# Rainbow_F103C_Sch.net
KiCad netlist of a schematic drawn in Altium Designer
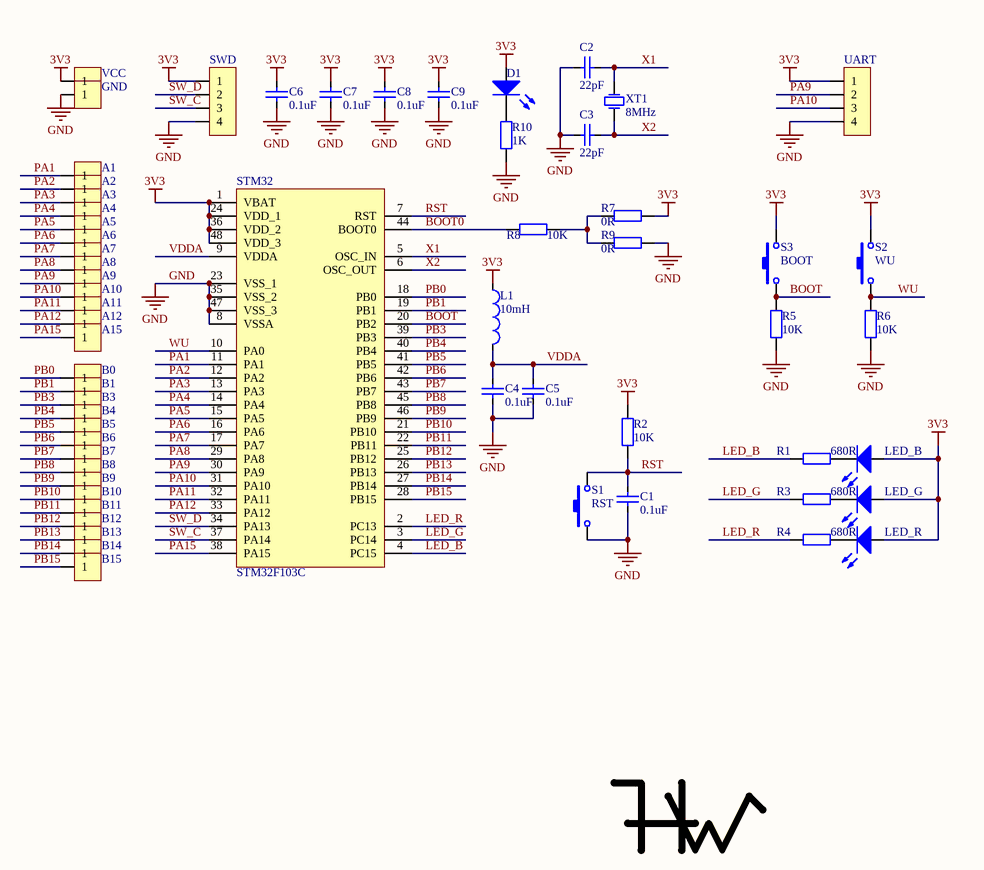
[diagram p0: Rainbow F103C_Sch.SchDoc]

(export (version "E")
  (design (tool "Eeschema 10.0.6"))
  (components
    (comp (ref "A1")
      (value "HDR1X1_180_2.54")
      (footprint "PCB_Connector:HDR1X1_180_2.54")
      (description "Header")
      (libsource (lib "SCH_Connector") (part "HDR1X1_180_2.54"))
    )
    (comp (ref "A2")
      (value "HDR1X1_180_2.54")
      (footprint "PCB_Connector:HDR1X1_180_2.54")
      (description "Header")
      (libsource (lib "SCH_Connector") (part "HDR1X1_180_2.54"))
    )
    (comp (ref "A3")
      (value "HDR1X1_180_2.54")
      (footprint "PCB_Connector:HDR1X1_180_2.54")
      (description "Header")
      (libsource (lib "SCH_Connector") (part "HDR1X1_180_2.54"))
    )
    (comp (ref "A4")
      (value "HDR1X1_180_2.54")
      (footprint "PCB_Connector:HDR1X1_180_2.54")
      (description "Header")
      (libsource (lib "SCH_Connector") (part "HDR1X1_180_2.54"))
    )
    (comp (ref "A5")
      (value "HDR1X1_180_2.54")
      (footprint "PCB_Connector:HDR1X1_180_2.54")
      (description "Header")
      (libsource (lib "SCH_Connector") (part "HDR1X1_180_2.54"))
    )
    (comp (ref "A6")
      (value "HDR1X1_180_2.54")
      (footprint "PCB_Connector:HDR1X1_180_2.54")
      (description "Header")
      (libsource (lib "SCH_Connector") (part "HDR1X1_180_2.54"))
    )
    (comp (ref "A7")
      (value "HDR1X1_180_2.54")
      (footprint "PCB_Connector:HDR1X1_180_2.54")
      (description "Header")
      (libsource (lib "SCH_Connector") (part "HDR1X1_180_2.54"))
    )
    (comp (ref "A8")
      (value "HDR1X1_180_2.54")
      (footprint "PCB_Connector:HDR1X1_180_2.54")
      (description "Header")
      (libsource (lib "SCH_Connector") (part "HDR1X1_180_2.54"))
    )
    (comp (ref "A9")
      (value "HDR1X1_180_2.54")
      (footprint "PCB_Connector:HDR1X1_180_2.54")
      (description "Header")
      (libsource (lib "SCH_Connector") (part "HDR1X1_180_2.54"))
    )
    (comp (ref "A10")
      (value "HDR1X1_180_2.54")
      (footprint "PCB_Connector:HDR1X1_180_2.54")
      (description "Header")
      (libsource (lib "SCH_Connector") (part "HDR1X1_180_2.54"))
    )
    (comp (ref "A11")
      (value "HDR1X1_180_2.54")
      (footprint "PCB_Connector:HDR1X1_180_2.54")
      (description "Header")
      (libsource (lib "SCH_Connector") (part "HDR1X1_180_2.54"))
    )
    (comp (ref "A12")
      (value "HDR1X1_180_2.54")
      (footprint "PCB_Connector:HDR1X1_180_2.54")
      (description "Header")
      (libsource (lib "SCH_Connector") (part "HDR1X1_180_2.54"))
    )
    (comp (ref "A15")
      (value "HDR1X1_180_2.54")
      (footprint "PCB_Connector:HDR1X1_180_2.54")
      (description "Header")
      (libsource (lib "SCH_Connector") (part "HDR1X1_180_2.54"))
    )
    (comp (ref "B0")
      (value "HDR1X1_180_2.54")
      (footprint "PCB_Connector:HDR1X1_180_2.54")
      (description "Header")
      (libsource (lib "SCH_Connector") (part "HDR1X1_180_2.54"))
    )
    (comp (ref "B1")
      (value "HDR1X1_180_2.54")
      (footprint "PCB_Connector:HDR1X1_180_2.54")
      (description "Header")
      (libsource (lib "SCH_Connector") (part "HDR1X1_180_2.54"))
    )
    (comp (ref "B3")
      (value "HDR1X1_180_2.54")
      (footprint "PCB_Connector:HDR1X1_180_2.54")
      (description "Header")
      (libsource (lib "SCH_Connector") (part "HDR1X1_180_2.54"))
    )
    (comp (ref "B4")
      (value "HDR1X1_180_2.54")
      (footprint "PCB_Connector:HDR1X1_180_2.54")
      (description "Header")
      (libsource (lib "SCH_Connector") (part "HDR1X1_180_2.54"))
    )
    (comp (ref "B5")
      (value "HDR1X1_180_2.54")
      (footprint "PCB_Connector:HDR1X1_180_2.54")
      (description "Header")
      (libsource (lib "SCH_Connector") (part "HDR1X1_180_2.54"))
    )
    (comp (ref "B6")
      (value "HDR1X1_180_2.54")
      (footprint "PCB_Connector:HDR1X1_180_2.54")
      (description "Header")
      (libsource (lib "SCH_Connector") (part "HDR1X1_180_2.54"))
    )
    (comp (ref "B7")
      (value "HDR1X1_180_2.54")
      (footprint "PCB_Connector:HDR1X1_180_2.54")
      (description "Header")
      (libsource (lib "SCH_Connector") (part "HDR1X1_180_2.54"))
    )
    (comp (ref "B8")
      (value "HDR1X1_180_2.54")
      (footprint "PCB_Connector:HDR1X1_180_2.54")
      (description "Header")
      (libsource (lib "SCH_Connector") (part "HDR1X1_180_2.54"))
    )
    (comp (ref "B9")
      (value "HDR1X1_180_2.54")
      (footprint "PCB_Connector:HDR1X1_180_2.54")
      (description "Header")
      (libsource (lib "SCH_Connector") (part "HDR1X1_180_2.54"))
    )
    (comp (ref "B10")
      (value "HDR1X1_180_2.54")
      (footprint "PCB_Connector:HDR1X1_180_2.54")
      (description "Header")
      (libsource (lib "SCH_Connector") (part "HDR1X1_180_2.54"))
    )
    (comp (ref "B11")
      (value "HDR1X1_180_2.54")
      (footprint "PCB_Connector:HDR1X1_180_2.54")
      (description "Header")
      (libsource (lib "SCH_Connector") (part "HDR1X1_180_2.54"))
    )
    (comp (ref "B12")
      (value "HDR1X1_180_2.54")
      (footprint "PCB_Connector:HDR1X1_180_2.54")
      (description "Header")
      (libsource (lib "SCH_Connector") (part "HDR1X1_180_2.54"))
    )
    (comp (ref "B13")
      (value "HDR1X1_180_2.54")
      (footprint "PCB_Connector:HDR1X1_180_2.54")
      (description "Header")
      (libsource (lib "SCH_Connector") (part "HDR1X1_180_2.54"))
    )
    (comp (ref "B14")
      (value "HDR1X1_180_2.54")
      (footprint "PCB_Connector:HDR1X1_180_2.54")
      (description "Header")
      (libsource (lib "SCH_Connector") (part "HDR1X1_180_2.54"))
    )
    (comp (ref "B15")
      (value "HDR1X1_180_2.54")
      (footprint "PCB_Connector:HDR1X1_180_2.54")
      (description "Header")
      (libsource (lib "SCH_Connector") (part "HDR1X1_180_2.54"))
    )
    (comp (ref "C1")
      (value "0.1uF")
      (footprint "PCB_Passive:CAP_0603")
      (description "Capacitor")
      (fields (field (name "Comment") "Cap_0603"))
      (libsource (lib "SCH_Passive") (part "Cap_0603"))
    )
    (comp (ref "C2")
      (value "22pF")
      (footprint "PCB_Passive:CAP_0603")
      (description "Capacitor")
      (fields (field (name "Comment") "Cap_0603"))
      (libsource (lib "SCH_Passive") (part "Cap_0603"))
    )
    (comp (ref "C3")
      (value "22pF")
      (footprint "PCB_Passive:CAP_0603")
      (description "Capacitor")
      (fields (field (name "Comment") "Cap_0603"))
      (libsource (lib "SCH_Passive") (part "Cap_0603"))
    )
    (comp (ref "C4")
      (value "0.1uF")
      (footprint "PCB_Passive:CAP_0603")
      (description "Capacitor")
      (fields (field (name "Comment") "Cap_0603"))
      (libsource (lib "SCH_Passive") (part "Cap_0603"))
    )
    (comp (ref "C5")
      (value "0.1uF")
      (footprint "PCB_Passive:CAP_0603")
      (description "Capacitor")
      (fields (field (name "Comment") "Cap_0603"))
      (libsource (lib "SCH_Passive") (part "Cap_0603"))
    )
    (comp (ref "C6")
      (value "0.1uF")
      (footprint "PCB_Passive:CAP_0603")
      (description "Capacitor")
      (fields (field (name "Comment") "Cap_0603"))
      (libsource (lib "SCH_Passive") (part "Cap_0603"))
    )
    (comp (ref "C7")
      (value "0.1uF")
      (footprint "PCB_Passive:CAP_0603")
      (description "Capacitor")
      (fields (field (name "Comment") "Cap_0603"))
      (libsource (lib "SCH_Passive") (part "Cap_0603"))
    )
    (comp (ref "C8")
      (value "0.1uF")
      (footprint "PCB_Passive:CAP_0603")
      (description "Capacitor")
      (fields (field (name "Comment") "Cap_0603"))
      (libsource (lib "SCH_Passive") (part "Cap_0603"))
    )
    (comp (ref "C9")
      (value "0.1uF")
      (footprint "PCB_Passive:CAP_0603")
      (description "Capacitor")
      (fields (field (name "Comment") "Cap_0603"))
      (libsource (lib "SCH_Passive") (part "Cap_0603"))
    )
    (comp (ref "D1")
      (value "LED_0603_BLUE")
      (footprint "PCB_Active:LED_0603_BLUE")
      (description "LED")
      (libsource (lib "SCH_Active") (part "LED_0603_BLUE"))
    )
    (comp (ref "GND")
      (value "HDR1X1_180_2.54")
      (footprint "PCB_Connector:HDR1X1_180_2.54")
      (description "Header")
      (libsource (lib "SCH_Connector") (part "HDR1X1_180_2.54"))
    )
    (comp (ref "L1")
      (value "10mH")
      (footprint "PCB_Passive:IND_0603")
      (description "Inductor")
      (fields (field (name "Comment") "Ind_0603"))
      (libsource (lib "SCH_Passive") (part "Ind_0603"))
    )
    (comp (ref "LED_B")
      (value "LED_0603_BLUE")
      (footprint "PCB_Active:LED_0603_BLUE")
      (description "LED")
      (libsource (lib "SCH_Active") (part "LED_0603_BLUE"))
    )
    (comp (ref "LED_G")
      (value "LED_0603_GREEN")
      (footprint "PCB_Active:LED_0603_GREEN")
      (description "LED")
      (libsource (lib "SCH_Active") (part "LED_0603_GREEN"))
    )
    (comp (ref "LED_R")
      (value "LED_0603_RED")
      (footprint "PCB_Active:LED_0603_RED")
      (description "LED")
      (libsource (lib "SCH_Active") (part "LED_0603_RED"))
    )
    (comp (ref "Mark1")
      (value "Mark")
      (footprint "PCB_Mark:HW_Mark")
      (libsource (lib "SCH_Mark") (part "HW"))
    )
    (comp (ref "R1")
      (value "680R")
      (footprint "PCB_Passive:RES_0603")
      (description "Resistor")
      (fields (field (name "Comment") "Res_0603"))
      (libsource (lib "SCH_Passive") (part "Res_0603"))
    )
    (comp (ref "R2")
      (value "10K")
      (footprint "PCB_Passive:RES_0603")
      (description "Resistor")
      (fields (field (name "Comment") "Res_0603"))
      (libsource (lib "") (part "Res_0603_1"))
    )
    (comp (ref "R3")
      (value "680R")
      (footprint "PCB_Passive:RES_0603")
      (description "Resistor")
      (fields (field (name "Comment") "Res_0603"))
      (libsource (lib "SCH_Passive") (part "Res_0603"))
    )
    (comp (ref "R4")
      (value "680R")
      (footprint "PCB_Passive:RES_0603")
      (description "Resistor")
      (fields (field (name "Comment") "Res_0603"))
      (libsource (lib "SCH_Passive") (part "Res_0603"))
    )
    (comp (ref "R5")
      (value "10K")
      (footprint "PCB_Passive:RES_0603")
      (description "Resistor")
      (fields (field (name "Comment") "Res_0603"))
      (libsource (lib "") (part "Res_0603_1"))
    )
    (comp (ref "R6")
      (value "10K")
      (footprint "PCB_Passive:RES_0603")
      (description "Resistor")
      (fields (field (name "Comment") "Res_0603"))
      (libsource (lib "") (part "Res_0603_1"))
    )
    (comp (ref "R7")
      (value "0R")
      (footprint "PCB_Passive:RES_0603")
      (description "Resistor")
      (fields (field (name "Comment") "Res_0603"))
      (libsource (lib "SCH_Passive") (part "Res_0603"))
    )
    (comp (ref "R8")
      (value "10K")
      (footprint "PCB_Passive:RES_0603")
      (description "Resistor")
      (fields (field (name "Comment") "Res_0603"))
      (libsource (lib "SCH_Passive") (part "Res_0603"))
    )
    (comp (ref "R9")
      (value "0R")
      (footprint "PCB_Passive:RES_0603")
      (description "Resistor")
      (fields (field (name "Comment") "Res_0603"))
      (libsource (lib "SCH_Passive") (part "Res_0603"))
    )
    (comp (ref "R10")
      (value "1K")
      (footprint "PCB_Passive:RES_0603")
      (description "Resistor")
      (fields (field (name "Comment") "Res_0603"))
      (libsource (lib "") (part "Res_0603_2"))
    )
    (comp (ref "S1")
      (value "RST")
      (footprint "PCB_Switch:BT_TACT")
      (description "Switch")
      (libsource (lib "SCH_Switch") (part "BT_TACT"))
    )
    (comp (ref "S2")
      (value "WU")
      (footprint "PCB_Switch:BT_TACT")
      (description "Switch")
      (libsource (lib "SCH_Switch") (part "BT_TACT"))
    )
    (comp (ref "S3")
      (value "BOOT")
      (footprint "PCB_Switch:BT_TACT")
      (description "Switch")
      (libsource (lib "SCH_Switch") (part "BT_TACT"))
    )
    (comp (ref "STM32")
      (value "STM32F103C")
      (footprint "PCB_IC:STM32F_48")
      (description "MCU")
      (libsource (lib "SCH_IC") (part "STM32F103C"))
    )
    (comp (ref "SWD")
      (value "HDR1X4_90F_2.54")
      (footprint "PCB_Connector:HDR1X4_90F_2.54")
      (description "Header")
      (libsource (lib "SCH_Connector") (part "HDR1X4_90F_2.54"))
    )
    (comp (ref "UART")
      (value "HDR1X4_90F_2.54")
      (footprint "PCB_Connector:HDR1X4_90F_2.54")
      (description "Header")
      (libsource (lib "SCH_Connector") (part "HDR1X4_90F_2.54"))
    )
    (comp (ref "VCC")
      (value "HDR1X1_180_2.54")
      (footprint "PCB_Connector:HDR1X1_180_2.54")
      (description "Header")
      (libsource (lib "SCH_Connector") (part "HDR1X1_180_2.54"))
    )
    (comp (ref "XT1")
      (value "8MHz")
      (footprint "PCB_Oscillator:XTAL_5032")
      (description "Crystal Oscillator")
      (fields (field (name "Comment") "XTAL_5032") (field (name "PUBLISHER") "Altium Limited"))
      (libsource (lib "SCH_Oscillator") (part "XTAL_5032"))
    )
  )
  (nets
    (net (code "1") (name "/BOOT") (class "Default")
      (node (ref "R5") (pin "1") (pinfunction "1_1") (pintype "passive"))
      (node (ref "S3") (pin "1") (pinfunction "1_1") (pintype "passive"))
      (node (ref "STM32") (pin "20") (pinfunction "PB2_20") (pintype "passive"))
    )
    (net (code "2") (name "/BOOT0") (class "Default")
      (node (ref "R8") (pin "1") (pinfunction "1_1") (pintype "passive"))
      (node (ref "STM32") (pin "44") (pinfunction "BOOT0_44") (pintype "passive"))
    )
    (net (code "3") (name "/LED_B") (class "Default")
      (node (ref "R1") (pin "1") (pinfunction "1_1") (pintype "passive"))
      (node (ref "STM32") (pin "4") (pinfunction "PC15_4") (pintype "passive"))
    )
    (net (code "4") (name "/LED_G") (class "Default")
      (node (ref "R3") (pin "1") (pinfunction "1_1") (pintype "passive"))
      (node (ref "STM32") (pin "3") (pinfunction "PC14_3") (pintype "passive"))
    )
    (net (code "5") (name "/LED_R") (class "Default")
      (node (ref "R4") (pin "1") (pinfunction "1_1") (pintype "passive"))
      (node (ref "STM32") (pin "2") (pinfunction "PC13_2") (pintype "passive"))
    )
    (net (code "6") (name "/PA1") (class "Default")
      (node (ref "A1") (pin "1") (pinfunction "1_1") (pintype "passive"))
      (node (ref "STM32") (pin "11") (pinfunction "PA1_11") (pintype "passive"))
    )
    (net (code "7") (name "/PA2") (class "Default")
      (node (ref "A2") (pin "1") (pinfunction "1_1") (pintype "passive"))
      (node (ref "STM32") (pin "12") (pinfunction "PA2_12") (pintype "passive"))
    )
    (net (code "8") (name "/PA3") (class "Default")
      (node (ref "A3") (pin "1") (pinfunction "1_1") (pintype "passive"))
      (node (ref "STM32") (pin "13") (pinfunction "PA3_13") (pintype "passive"))
    )
    (net (code "9") (name "/PA4") (class "Default")
      (node (ref "A4") (pin "1") (pinfunction "1_1") (pintype "passive"))
      (node (ref "STM32") (pin "14") (pinfunction "PA4_14") (pintype "passive"))
    )
    (net (code "10") (name "/PA5") (class "Default")
      (node (ref "A5") (pin "1") (pinfunction "1_1") (pintype "passive"))
      (node (ref "STM32") (pin "15") (pinfunction "PA5_15") (pintype "passive"))
    )
    (net (code "11") (name "/PA6") (class "Default")
      (node (ref "A6") (pin "1") (pinfunction "1_1") (pintype "passive"))
      (node (ref "STM32") (pin "16") (pinfunction "PA6_16") (pintype "passive"))
    )
    (net (code "12") (name "/PA7") (class "Default")
      (node (ref "A7") (pin "1") (pinfunction "1_1") (pintype "passive"))
      (node (ref "STM32") (pin "17") (pinfunction "PA7_17") (pintype "passive"))
    )
    (net (code "13") (name "/PA8") (class "Default")
      (node (ref "A8") (pin "1") (pinfunction "1_1") (pintype "passive"))
      (node (ref "STM32") (pin "29") (pinfunction "PA8_29") (pintype "passive"))
    )
    (net (code "14") (name "/PA9") (class "Default")
      (node (ref "A9") (pin "1") (pinfunction "1_1") (pintype "passive"))
      (node (ref "STM32") (pin "30") (pinfunction "PA9_30") (pintype "passive"))
      (node (ref "UART") (pin "2") (pinfunction "2_2") (pintype "passive"))
    )
    (net (code "15") (name "/PA10") (class "Default")
      (node (ref "A10") (pin "1") (pinfunction "1_1") (pintype "passive"))
      (node (ref "STM32") (pin "31") (pinfunction "PA10_31") (pintype "passive"))
      (node (ref "UART") (pin "3") (pinfunction "3_3") (pintype "passive"))
    )
    (net (code "16") (name "/PA11") (class "Default")
      (node (ref "A11") (pin "1") (pinfunction "1_1") (pintype "passive"))
      (node (ref "STM32") (pin "32") (pinfunction "PA11_32") (pintype "passive"))
    )
    (net (code "17") (name "/PA12") (class "Default")
      (node (ref "A12") (pin "1") (pinfunction "1_1") (pintype "passive"))
      (node (ref "STM32") (pin "33") (pinfunction "PA12_33") (pintype "passive"))
    )
    (net (code "18") (name "/PA15") (class "Default")
      (node (ref "A15") (pin "1") (pinfunction "1_1") (pintype "passive"))
      (node (ref "STM32") (pin "38") (pinfunction "PA15_38") (pintype "passive"))
    )
    (net (code "19") (name "/PB0") (class "Default")
      (node (ref "B0") (pin "1") (pinfunction "1_1") (pintype "passive"))
      (node (ref "STM32") (pin "18") (pinfunction "PB0_18") (pintype "passive"))
    )
    (net (code "20") (name "/PB1") (class "Default")
      (node (ref "B1") (pin "1") (pinfunction "1_1") (pintype "passive"))
      (node (ref "STM32") (pin "19") (pinfunction "PB1_19") (pintype "passive"))
    )
    (net (code "21") (name "/PB3") (class "Default")
      (node (ref "B3") (pin "1") (pinfunction "1_1") (pintype "passive"))
      (node (ref "STM32") (pin "39") (pinfunction "PB3_39") (pintype "passive"))
    )
    (net (code "22") (name "/PB4") (class "Default")
      (node (ref "B4") (pin "1") (pinfunction "1_1") (pintype "passive"))
      (node (ref "STM32") (pin "40") (pinfunction "PB4_40") (pintype "passive"))
    )
    (net (code "23") (name "/PB5") (class "Default")
      (node (ref "B5") (pin "1") (pinfunction "1_1") (pintype "passive"))
      (node (ref "STM32") (pin "41") (pinfunction "PB5_41") (pintype "passive"))
    )
    (net (code "24") (name "/PB6") (class "Default")
      (node (ref "B6") (pin "1") (pinfunction "1_1") (pintype "passive"))
      (node (ref "STM32") (pin "42") (pinfunction "PB6_42") (pintype "passive"))
    )
    (net (code "25") (name "/PB7") (class "Default")
      (node (ref "B7") (pin "1") (pinfunction "1_1") (pintype "passive"))
      (node (ref "STM32") (pin "43") (pinfunction "PB7_43") (pintype "passive"))
    )
    (net (code "26") (name "/PB8") (class "Default")
      (node (ref "B8") (pin "1") (pinfunction "1_1") (pintype "passive"))
      (node (ref "STM32") (pin "45") (pinfunction "PB8_45") (pintype "passive"))
    )
    (net (code "27") (name "/PB9") (class "Default")
      (node (ref "B9") (pin "1") (pinfunction "1_1") (pintype "passive"))
      (node (ref "STM32") (pin "46") (pinfunction "PB9_46") (pintype "passive"))
    )
    (net (code "28") (name "/PB10") (class "Default")
      (node (ref "B10") (pin "1") (pinfunction "1_1") (pintype "passive"))
      (node (ref "STM32") (pin "21") (pinfunction "PB10_21") (pintype "passive"))
    )
    (net (code "29") (name "/PB11") (class "Default")
      (node (ref "B11") (pin "1") (pinfunction "1_1") (pintype "passive"))
      (node (ref "STM32") (pin "22") (pinfunction "PB11_22") (pintype "passive"))
    )
    (net (code "30") (name "/PB12") (class "Default")
      (node (ref "B12") (pin "1") (pinfunction "1_1") (pintype "passive"))
      (node (ref "STM32") (pin "25") (pinfunction "PB12_25") (pintype "passive"))
    )
    (net (code "31") (name "/PB13") (class "Default")
      (node (ref "B13") (pin "1") (pinfunction "1_1") (pintype "passive"))
      (node (ref "STM32") (pin "26") (pinfunction "PB13_26") (pintype "passive"))
    )
    (net (code "32") (name "/PB14") (class "Default")
      (node (ref "B14") (pin "1") (pinfunction "1_1") (pintype "passive"))
      (node (ref "STM32") (pin "27") (pinfunction "PB14_27") (pintype "passive"))
    )
    (net (code "33") (name "/PB15") (class "Default")
      (node (ref "B15") (pin "1") (pinfunction "1_1") (pintype "passive"))
      (node (ref "STM32") (pin "28") (pinfunction "PB15_28") (pintype "passive"))
    )
    (net (code "34") (name "/RST") (class "Default")
      (node (ref "C1") (pin "1") (pinfunction "1_1") (pintype "passive"))
      (node (ref "R2") (pin "2") (pinfunction "2_2") (pintype "passive"))
      (node (ref "S1") (pin "2") (pinfunction "2_2") (pintype "passive"))
      (node (ref "STM32") (pin "7") (pinfunction "RST_7") (pintype "passive"))
    )
    (net (code "35") (name "/SW_C") (class "Default")
      (node (ref "STM32") (pin "37") (pinfunction "PA14_37") (pintype "passive"))
      (node (ref "SWD") (pin "3") (pinfunction "3_3") (pintype "passive"))
    )
    (net (code "36") (name "/SW_D") (class "Default")
      (node (ref "STM32") (pin "34") (pinfunction "PA13_34") (pintype "passive"))
      (node (ref "SWD") (pin "2") (pinfunction "2_2") (pintype "passive"))
    )
    (net (code "37") (name "/VDDA") (class "Default")
      (node (ref "C4") (pin "1") (pinfunction "1_1") (pintype "passive"))
      (node (ref "C5") (pin "1") (pinfunction "1_1") (pintype "passive"))
      (node (ref "L1") (pin "2") (pinfunction "2_2") (pintype "passive"))
      (node (ref "STM32") (pin "9") (pinfunction "VDDA_9") (pintype "passive"))
    )
    (net (code "38") (name "/WU") (class "Default")
      (node (ref "R6") (pin "1") (pinfunction "1_1") (pintype "passive"))
      (node (ref "S2") (pin "1") (pinfunction "1_1") (pintype "passive"))
      (node (ref "STM32") (pin "10") (pinfunction "PA0_10") (pintype "passive"))
    )
    (net (code "39") (name "/X1") (class "Default")
      (node (ref "C2") (pin "2") (pinfunction "2_2") (pintype "passive"))
      (node (ref "STM32") (pin "5") (pinfunction "OSC_IN_5") (pintype "passive"))
      (node (ref "XT1") (pin "2") (pinfunction "OSC2_2") (pintype "passive"))
    )
    (net (code "40") (name "/X2") (class "Default")
      (node (ref "C3") (pin "2") (pinfunction "2_2") (pintype "passive"))
      (node (ref "STM32") (pin "6") (pinfunction "OSC_OUT_6") (pintype "passive"))
      (node (ref "XT1") (pin "1") (pinfunction "OSC1_1") (pintype "passive"))
    )
    (net (code "41") (name "3V3") (class "Default")
      (node (ref "C6") (pin "2") (pinfunction "2_2") (pintype "passive"))
      (node (ref "C7") (pin "2") (pinfunction "2_2") (pintype "passive"))
      (node (ref "C8") (pin "2") (pinfunction "2_2") (pintype "passive"))
      (node (ref "C9") (pin "2") (pinfunction "2_2") (pintype "passive"))
      (node (ref "D1") (pin "1") (pinfunction "A_1") (pintype "passive"))
      (node (ref "L1") (pin "1") (pinfunction "1_1") (pintype "passive"))
      (node (ref "LED_B") (pin "1") (pinfunction "A_1") (pintype "passive"))
      (node (ref "LED_G") (pin "1") (pinfunction "A_1") (pintype "passive"))
      (node (ref "LED_R") (pin "1") (pinfunction "A_1") (pintype "passive"))
      (node (ref "R2") (pin "1") (pinfunction "1_1") (pintype "passive"))
      (node (ref "R7") (pin "2") (pinfunction "2_2") (pintype "passive"))
      (node (ref "S2") (pin "2") (pinfunction "2_2") (pintype "passive"))
      (node (ref "S3") (pin "2") (pinfunction "2_2") (pintype "passive"))
      (node (ref "STM32") (pin "1") (pinfunction "VBAT_1") (pintype "passive"))
      (node (ref "STM32") (pin "24") (pinfunction "VDD_1_24") (pintype "passive"))
      (node (ref "STM32") (pin "36") (pinfunction "VDD_2_36") (pintype "passive"))
      (node (ref "STM32") (pin "48") (pinfunction "VDD_3_48") (pintype "passive"))
      (node (ref "SWD") (pin "1") (pinfunction "1_1") (pintype "passive"))
      (node (ref "UART") (pin "1") (pinfunction "1_1") (pintype "passive"))
      (node (ref "VCC") (pin "1") (pinfunction "1_1") (pintype "passive"))
    )
    (net (code "42") (name "GND") (class "Default")
      (node (ref "C1") (pin "2") (pinfunction "2_2") (pintype "passive"))
      (node (ref "C2") (pin "1") (pinfunction "1_1") (pintype "passive"))
      (node (ref "C3") (pin "1") (pinfunction "1_1") (pintype "passive"))
      (node (ref "C4") (pin "2") (pinfunction "2_2") (pintype "passive"))
      (node (ref "C5") (pin "2") (pinfunction "2_2") (pintype "passive"))
      (node (ref "C6") (pin "1") (pinfunction "1_1") (pintype "passive"))
      (node (ref "C7") (pin "1") (pinfunction "1_1") (pintype "passive"))
      (node (ref "C8") (pin "1") (pinfunction "1_1") (pintype "passive"))
      (node (ref "C9") (pin "1") (pinfunction "1_1") (pintype "passive"))
      (node (ref "GND") (pin "1") (pinfunction "1_1") (pintype "passive"))
      (node (ref "R10") (pin "1") (pinfunction "1_1") (pintype "passive"))
      (node (ref "R5") (pin "2") (pinfunction "2_2") (pintype "passive"))
      (node (ref "R6") (pin "2") (pinfunction "2_2") (pintype "passive"))
      (node (ref "R9") (pin "2") (pinfunction "2_2") (pintype "passive"))
      (node (ref "S1") (pin "1") (pinfunction "1_1") (pintype "passive"))
      (node (ref "STM32") (pin "23") (pinfunction "VSS_1_23") (pintype "passive"))
      (node (ref "STM32") (pin "35") (pinfunction "VSS_2_35") (pintype "passive"))
      (node (ref "STM32") (pin "47") (pinfunction "VSS_3_47") (pintype "passive"))
      (node (ref "STM32") (pin "8") (pinfunction "VSSA_8") (pintype "passive"))
      (node (ref "SWD") (pin "4") (pinfunction "4_4") (pintype "passive"))
      (node (ref "UART") (pin "4") (pinfunction "4_4") (pintype "passive"))
    )
    (net (code "43") (name "Net-(D1-K)") (class "Default")
      (node (ref "D1") (pin "2") (pinfunction "K_2") (pintype "passive"))
      (node (ref "R10") (pin "2") (pinfunction "2_2") (pintype "passive"))
    )
    (net (code "44") (name "Net-(LED_B-K)") (class "Default")
      (node (ref "LED_B") (pin "2") (pinfunction "K_2") (pintype "passive"))
      (node (ref "R1") (pin "2") (pinfunction "2_2") (pintype "passive"))
    )
    (net (code "45") (name "Net-(LED_G-K)") (class "Default")
      (node (ref "LED_G") (pin "2") (pinfunction "K_2") (pintype "passive"))
      (node (ref "R3") (pin "2") (pinfunction "2_2") (pintype "passive"))
    )
    (net (code "46") (name "Net-(LED_R-K)") (class "Default")
      (node (ref "LED_R") (pin "2") (pinfunction "K_2") (pintype "passive"))
      (node (ref "R4") (pin "2") (pinfunction "2_2") (pintype "passive"))
    )
    (net (code "47") (name "Net-(R7-Pad1)") (class "Default")
      (node (ref "R7") (pin "1") (pinfunction "1_1") (pintype "passive"))
      (node (ref "R8") (pin "2") (pinfunction "2_2") (pintype "passive"))
      (node (ref "R9") (pin "1") (pinfunction "1_1") (pintype "passive"))
    )
  )
)
